# mosfet.net
KiCad netlist of a schematic drawn in EAGLE
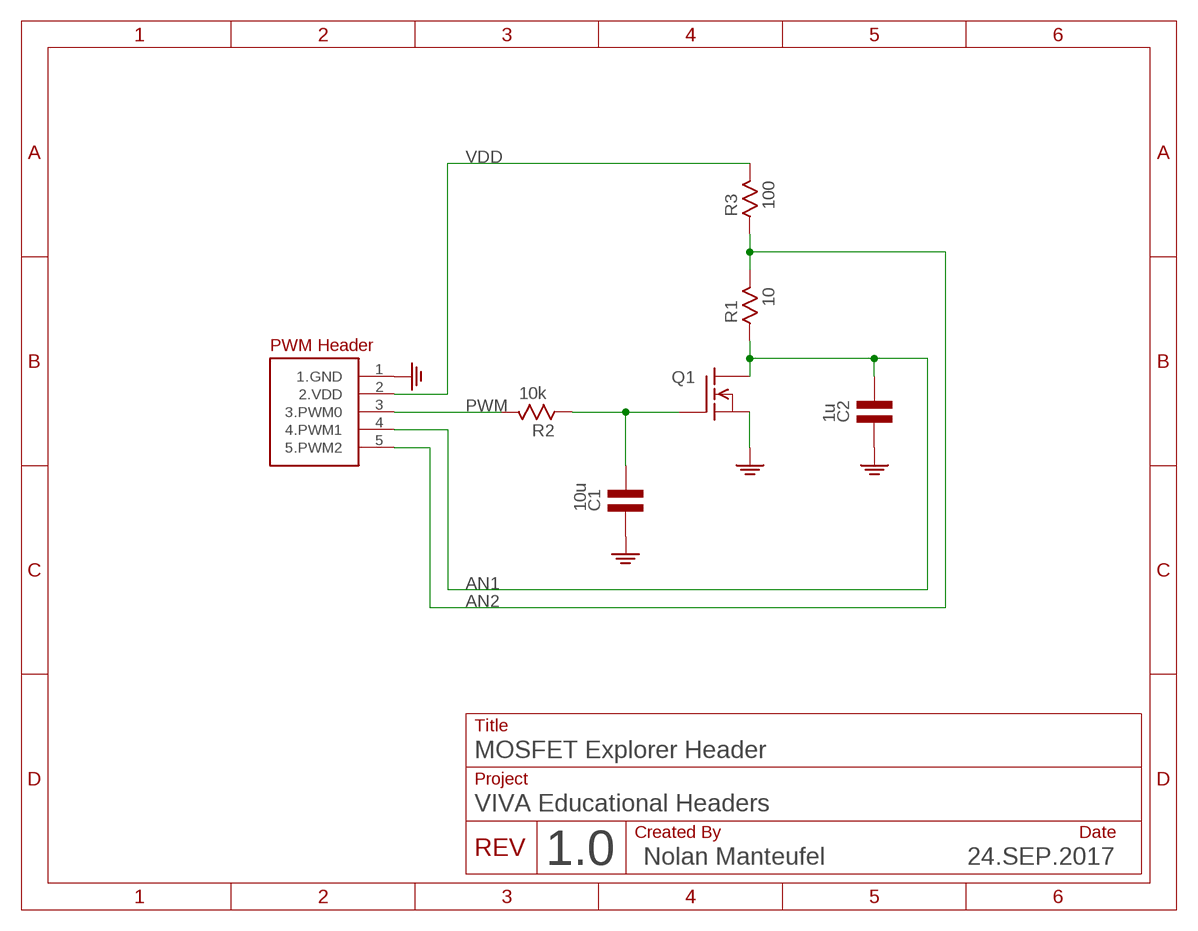
[diagram p0: schematic, sheet 1]

(export (version "E")
  (design (tool "Eeschema 10.0.6"))
  (components
    (comp (ref "C1")
      (value "10u")
      (footprint "eagle-import:C0805")
      (libsource (lib "eagle-import") (part "C0805"))
    )
    (comp (ref "C2")
      (value "1u")
      (footprint "eagle-import:C0805")
      (libsource (lib "eagle-import") (part "C0805"))
    )
    (comp (ref "Q1")
      (value "N-MOSFETNX7002AK")
      (footprint "eagle-import:SOT23")
      (libsource (lib "eagle-import") (part "N-MOSFETNX7002AK"))
    )
    (comp (ref "R1")
      (value "10")
      (footprint "eagle-import:R0805")
      (libsource (lib "eagle-import") (part "R0805"))
    )
    (comp (ref "R2")
      (value "10k")
      (footprint "eagle-import:R0805")
      (libsource (lib "eagle-import") (part "R0805"))
    )
    (comp (ref "R3")
      (value "100")
      (footprint "eagle-import:R0805")
      (libsource (lib "eagle-import") (part "R0805"))
    )
    (comp (ref "U$1")
      (value "VIVA-HEADER-PWM-XS")
      (footprint "eagle-import:PINS_5")
      (libsource (lib "eagle-import") (part "VIVA-HEADER-PWM-XS"))
    )
  )
  (nets
    (net (code "1") (name "/AN1") (class "Default")
      (node (ref "C2") (pin "2") (pinfunction "P$2_2") (pintype "passive"))
      (node (ref "Q1") (pin "3") (pinfunction "D_3") (pintype "passive"))
      (node (ref "R1") (pin "1") (pinfunction "P$1_1") (pintype "bidirectional"))
      (node (ref "U$1") (pin "4") (pinfunction "4.PWM1_4") (pintype "bidirectional"))
    )
    (net (code "2") (name "/AN2") (class "Default")
      (node (ref "C1") (pin "2") (pinfunction "P$2_2") (pintype "passive"))
      (node (ref "Q1") (pin "1") (pinfunction "G_1") (pintype "passive"))
      (node (ref "R1") (pin "2") (pinfunction "P$2_2") (pintype "bidirectional"))
      (node (ref "R2") (pin "1") (pinfunction "P$1_1") (pintype "bidirectional"))
      (node (ref "R3") (pin "1") (pinfunction "P$1_1") (pintype "bidirectional"))
      (node (ref "U$1") (pin "5") (pinfunction "5.PWM2_5") (pintype "bidirectional"))
    )
    (net (code "3") (name "/PWM") (class "Default")
      (node (ref "R2") (pin "2") (pinfunction "P$2_2") (pintype "bidirectional"))
      (node (ref "U$1") (pin "3") (pinfunction "3.PWM0_3") (pintype "bidirectional"))
    )
    (net (code "4") (name "/VDD") (class "Default")
      (node (ref "R3") (pin "2") (pinfunction "P$2_2") (pintype "bidirectional"))
      (node (ref "U$1") (pin "2") (pinfunction "2.VDD_2") (pintype "bidirectional"))
    )
    (net (code "5") (name "GND") (class "Default")
      (node (ref "C1") (pin "1") (pinfunction "P$1_1") (pintype "passive"))
      (node (ref "C2") (pin "1") (pinfunction "P$1_1") (pintype "passive"))
      (node (ref "Q1") (pin "2") (pinfunction "S_2") (pintype "passive"))
      (node (ref "U$1") (pin "1") (pinfunction "1.GND_1") (pintype "bidirectional"))
    )
  )
)
